# wordclockv0_1.net
KiCad netlist of a schematic drawn in EAGLE
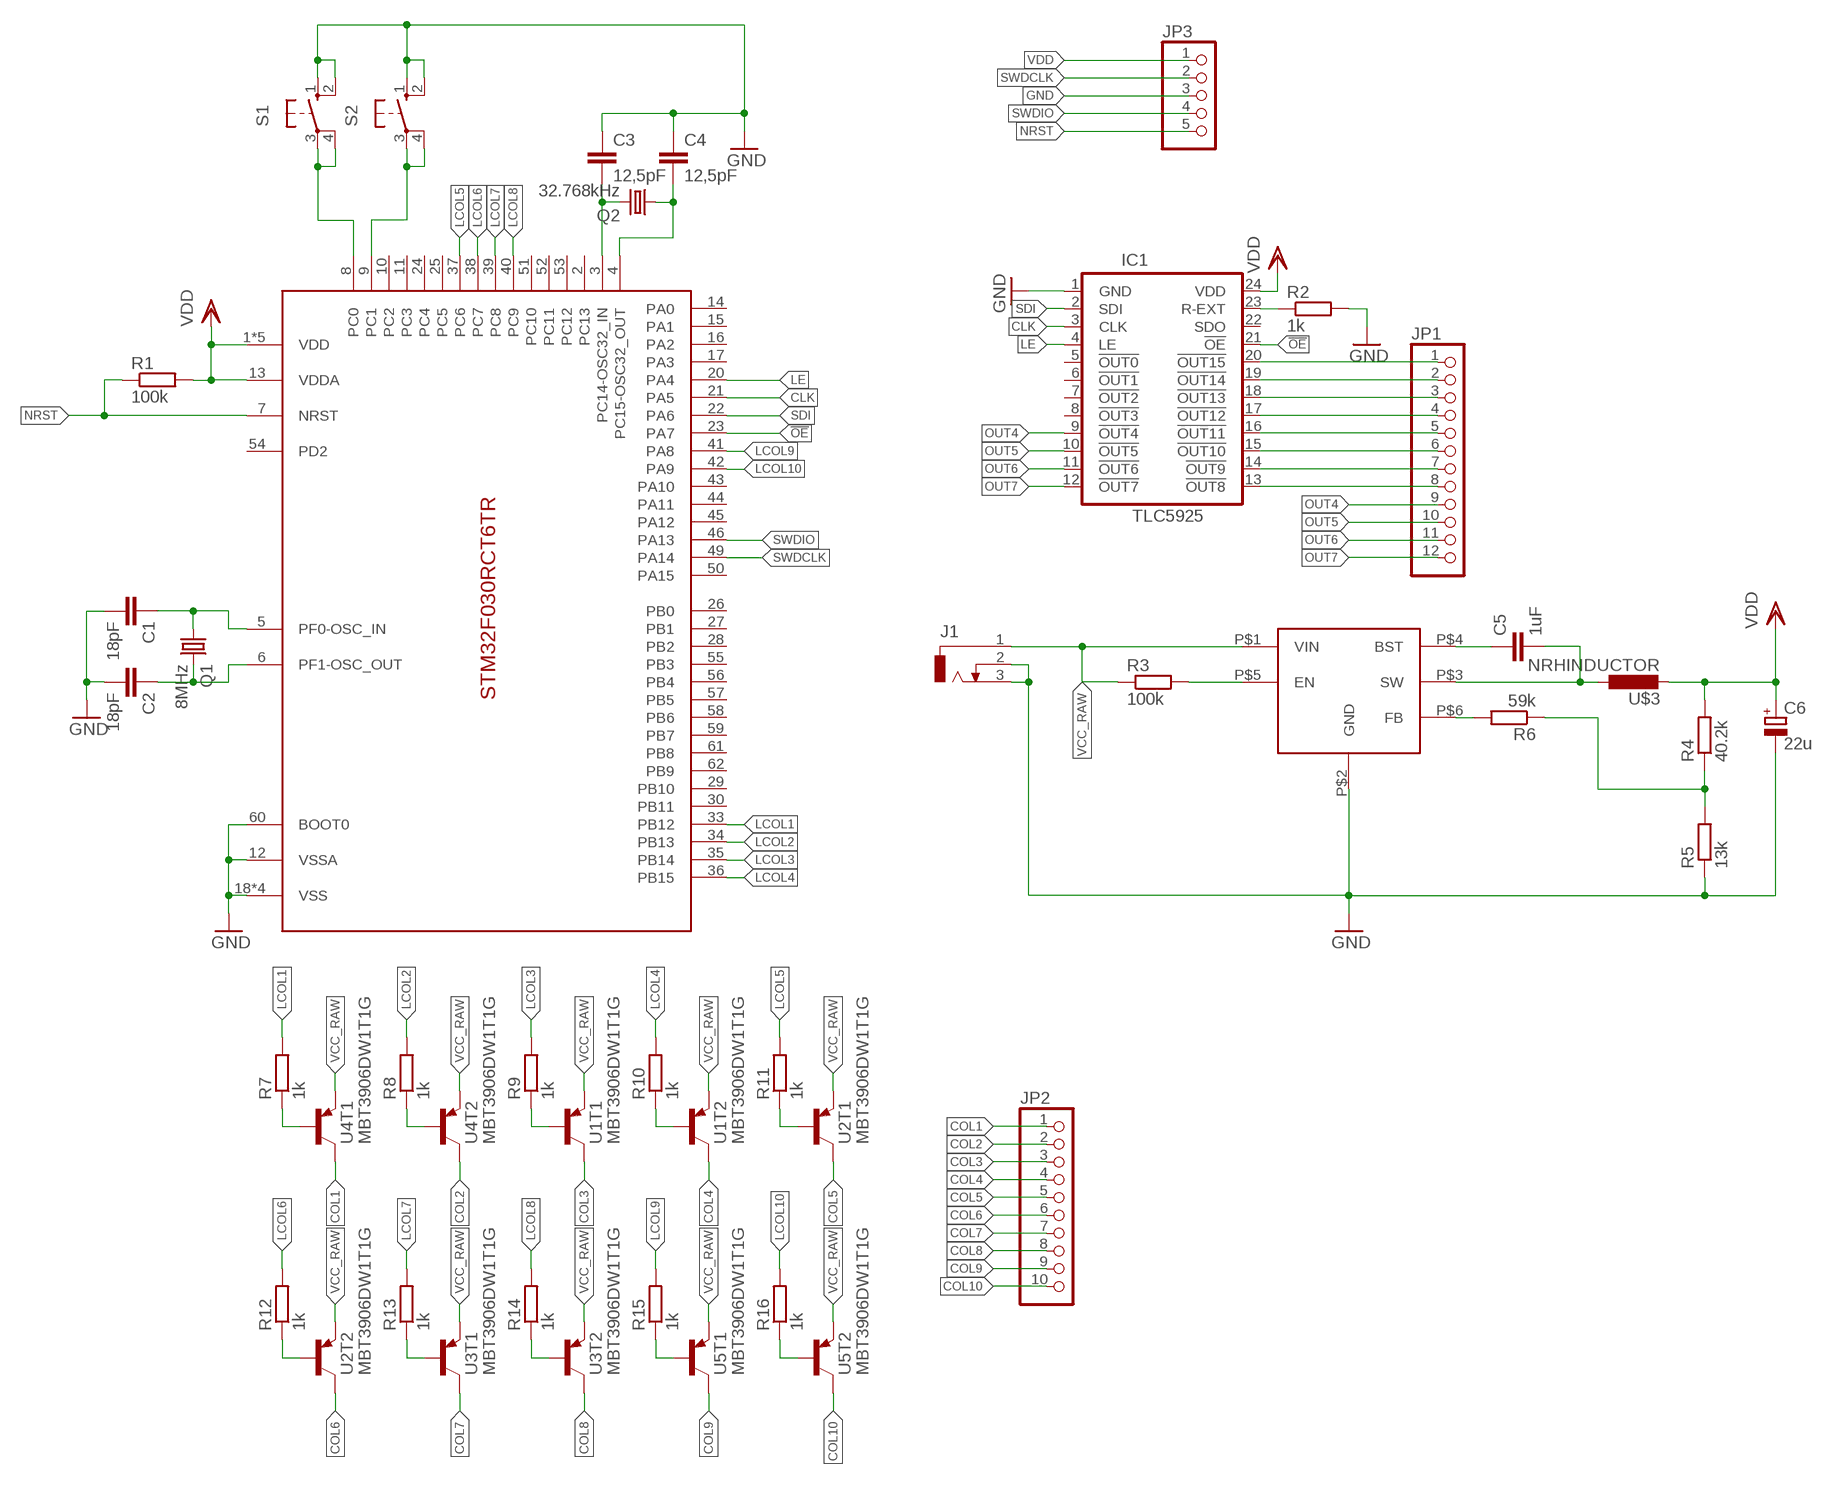
[diagram p0: schematic, sheet 1]

(export (version "E")
  (design (tool "Eeschema 10.0.6"))
  (components
    (comp (ref "C1")
      (value "18pF")
      (footprint "eagle-import:C0402")
      (libsource (lib "eagle-import") (part "C-EUC0402"))
    )
    (comp (ref "C2")
      (value "18pF")
      (footprint "eagle-import:C0402")
      (libsource (lib "eagle-import") (part "rcl_334_C-EUC0402"))
    )
    (comp (ref "C3")
      (value "12,5pF")
      (footprint "eagle-import:C0402")
      (libsource (lib "eagle-import") (part "C-EUC0402"))
    )
    (comp (ref "C4")
      (value "12,5pF")
      (footprint "eagle-import:C0402")
      (libsource (lib "eagle-import") (part "rcl_334_C-EUC0402"))
    )
    (comp (ref "C5")
      (value "1uF")
      (footprint "eagle-import:C0805")
      (libsource (lib "eagle-import") (part "C-EUC0805"))
    )
    (comp (ref "C6")
      (value "22u")
      (footprint "eagle-import:153CLV-0405")
      (libsource (lib "eagle-import") (part "CPOL-EU153CLV-0405"))
    )
    (comp (ref "IC1")
      (value "TLC5925")
      (footprint "eagle-import:SO24W")
      (libsource (lib "eagle-import") (part "TLC5925"))
    )
    (comp (ref "J1")
      (value "DCJ0303")
      (footprint "eagle-import:DCJ0303")
      (libsource (lib "eagle-import") (part "DCJ0303"))
    )
    (comp (ref "JP1")
      (value "PINHD-1X12")
      (footprint "eagle-import:1X12")
      (libsource (lib "eagle-import") (part "PINHD-1X12"))
    )
    (comp (ref "JP2")
      (value "PINHD-1X10")
      (footprint "eagle-import:1X10")
      (libsource (lib "eagle-import") (part "PINHD-1X10"))
    )
    (comp (ref "JP3")
      (value "PINHD-1X5")
      (footprint "eagle-import:1X05")
      (libsource (lib "eagle-import") (part "PINHD-1X5"))
    )
    (comp (ref "Q1")
      (value "8MHz")
      (footprint "eagle-import:HC49U-V")
      (libsource (lib "eagle-import") (part "crystal_204_CRYSTALHC49U-V"))
    )
    (comp (ref "Q2")
      (value "32.768kHz")
      (footprint "eagle-import:TC26V")
      (libsource (lib "eagle-import") (part "CRYSTALTC26V"))
    )
    (comp (ref "R1")
      (value "100k")
      (footprint "eagle-import:M1206")
      (libsource (lib "eagle-import") (part "R-EU_M1206"))
    )
    (comp (ref "R2")
      (value "1k")
      (footprint "eagle-import:M1206")
      (libsource (lib "eagle-import") (part "R-EU_M1206"))
    )
    (comp (ref "R3")
      (value "100k")
      (footprint "eagle-import:M1206")
      (libsource (lib "eagle-import") (part "R-EU_M1206"))
    )
    (comp (ref "R4")
      (value "40.2k")
      (footprint "eagle-import:M1206")
      (libsource (lib "eagle-import") (part "R-EU_M1206"))
    )
    (comp (ref "R5")
      (value "13k")
      (footprint "eagle-import:M1206")
      (libsource (lib "eagle-import") (part "R-EU_M1206"))
    )
    (comp (ref "R6")
      (value "59k")
      (footprint "eagle-import:M1206")
      (libsource (lib "eagle-import") (part "R-EU_M1206"))
    )
    (comp (ref "R7")
      (value "1k")
      (footprint "eagle-import:M1206")
      (libsource (lib "eagle-import") (part "R-EU_M1206"))
    )
    (comp (ref "R8")
      (value "1k")
      (footprint "eagle-import:M1206")
      (libsource (lib "eagle-import") (part "R-EU_M1206"))
    )
    (comp (ref "R9")
      (value "1k")
      (footprint "eagle-import:M1206")
      (libsource (lib "eagle-import") (part "R-EU_M1206"))
    )
    (comp (ref "R10")
      (value "1k")
      (footprint "eagle-import:M1206")
      (libsource (lib "eagle-import") (part "R-EU_M1206"))
    )
    (comp (ref "R11")
      (value "1k")
      (footprint "eagle-import:M1206")
      (libsource (lib "eagle-import") (part "R-EU_M1206"))
    )
    (comp (ref "R12")
      (value "1k")
      (footprint "eagle-import:M1206")
      (libsource (lib "eagle-import") (part "R-EU_M1206"))
    )
    (comp (ref "R13")
      (value "1k")
      (footprint "eagle-import:M1206")
      (libsource (lib "eagle-import") (part "R-EU_M1206"))
    )
    (comp (ref "R14")
      (value "1k")
      (footprint "eagle-import:M1206")
      (libsource (lib "eagle-import") (part "R-EU_M1206"))
    )
    (comp (ref "R15")
      (value "1k")
      (footprint "eagle-import:M1206")
      (libsource (lib "eagle-import") (part "R-EU_M1206"))
    )
    (comp (ref "R16")
      (value "1k")
      (footprint "eagle-import:M1206")
      (libsource (lib "eagle-import") (part "R-EU_M1206"))
    )
    (comp (ref "S1")
      (value "10-XX")
      (footprint "eagle-import:B3F-10XX")
      (fields (field (name "MPN") "B3F-1000"))
      (libsource (lib "eagle-import") (part "10-XX"))
    )
    (comp (ref "S2")
      (value "10-XX")
      (footprint "eagle-import:B3F-10XX")
      (fields (field (name "MPN") "B3F-1000"))
      (libsource (lib "eagle-import") (part "10-XX"))
    )
    (comp (ref "U$1")
      (value "STM32F030RCT6TRLQFP64")
      (footprint "eagle-import:LQFP64")
      (libsource (lib "eagle-import") (part "STM32F030RCT6TRLQFP64"))
    )
    (comp (ref "U$2")
      (value "AP65111A")
      (footprint "eagle-import:TSOT26")
      (libsource (lib "eagle-import") (part "AP65111A"))
    )
    (comp (ref "U$3")
      (value "NRHINDUCTOR")
      (footprint "eagle-import:NRHINDUCTOR")
      (libsource (lib "eagle-import") (part "NRHINDUCTOR"))
    )
    (comp (ref "U1")
      (value "MBT3906DW1T1G")
      (footprint "eagle-import:SOT363-INFINION")
      (libsource (lib "eagle-import") (part "MBT3906DW1T1G"))
    )
    (comp (ref "U2")
      (value "MBT3906DW1T1G")
      (footprint "eagle-import:SOT363-INFINION")
      (libsource (lib "eagle-import") (part "MBT3906DW1T1G"))
    )
    (comp (ref "U3")
      (value "MBT3906DW1T1G")
      (footprint "eagle-import:SOT363-INFINION")
      (libsource (lib "eagle-import") (part "MBT3906DW1T1G"))
    )
    (comp (ref "U4")
      (value "MBT3906DW1T1G")
      (footprint "eagle-import:SOT363-INFINION")
      (libsource (lib "eagle-import") (part "MBT3906DW1T1G"))
    )
    (comp (ref "U5")
      (value "MBT3906DW1T1G")
      (footprint "eagle-import:SOT363-INFINION")
      (libsource (lib "eagle-import") (part "MBT3906DW1T1G"))
    )
  )
  (nets
    (net (code "1") (name "/~{OE}") (class "Default")
      (node (ref "IC1") (pin "21") (pinfunction "~{OE}_21") (pintype "bidirectional"))
      (node (ref "U$1") (pin "23") (pinfunction "PA7_23") (pintype "bidirectional"))
    )
    (net (code "2") (name "CLK") (class "Default")
      (node (ref "IC1") (pin "3") (pinfunction "CLK_3") (pintype "input"))
      (node (ref "U$1") (pin "21") (pinfunction "PA5_21") (pintype "bidirectional"))
    )
    (net (code "3") (name "COL1") (class "Default")
      (node (ref "JP2") (pin "1") (pinfunction "1_1") (pintype "passive"))
      (node (ref "U4") (pin "6") (pinfunction "C_6") (pintype "passive"))
    )
    (net (code "4") (name "COL2") (class "Default")
      (node (ref "JP2") (pin "2") (pinfunction "2_2") (pintype "passive"))
      (node (ref "U4") (pin "3") (pinfunction "C_3") (pintype "passive"))
    )
    (net (code "5") (name "COL3") (class "Default")
      (node (ref "JP2") (pin "3") (pinfunction "3_3") (pintype "passive"))
      (node (ref "U1") (pin "6") (pinfunction "C_6") (pintype "passive"))
    )
    (net (code "6") (name "COL4") (class "Default")
      (node (ref "JP2") (pin "4") (pinfunction "4_4") (pintype "passive"))
      (node (ref "U1") (pin "3") (pinfunction "C_3") (pintype "passive"))
    )
    (net (code "7") (name "COL5") (class "Default")
      (node (ref "JP2") (pin "5") (pinfunction "5_5") (pintype "passive"))
      (node (ref "U2") (pin "6") (pinfunction "C_6") (pintype "passive"))
    )
    (net (code "8") (name "COL6") (class "Default")
      (node (ref "JP2") (pin "6") (pinfunction "6_6") (pintype "passive"))
      (node (ref "U2") (pin "3") (pinfunction "C_3") (pintype "passive"))
    )
    (net (code "9") (name "COL7") (class "Default")
      (node (ref "JP2") (pin "7") (pinfunction "7_7") (pintype "passive"))
      (node (ref "U3") (pin "6") (pinfunction "C_6") (pintype "passive"))
    )
    (net (code "10") (name "COL8") (class "Default")
      (node (ref "JP2") (pin "8") (pinfunction "8_8") (pintype "passive"))
      (node (ref "U3") (pin "3") (pinfunction "C_3") (pintype "passive"))
    )
    (net (code "11") (name "COL9") (class "Default")
      (node (ref "JP2") (pin "9") (pinfunction "9_9") (pintype "passive"))
      (node (ref "U5") (pin "6") (pinfunction "C_6") (pintype "passive"))
    )
    (net (code "12") (name "COL10") (class "Default")
      (node (ref "JP2") (pin "10") (pinfunction "10_10") (pintype "passive"))
      (node (ref "U5") (pin "3") (pinfunction "C_3") (pintype "passive"))
    )
    (net (code "13") (name "GND") (class "Default")
      (node (ref "C1") (pin "2") (pinfunction "2_2") (pintype "passive"))
      (node (ref "C2") (pin "2") (pinfunction "2_2") (pintype "passive"))
      (node (ref "C3") (pin "1") (pinfunction "1_1") (pintype "passive"))
      (node (ref "C4") (pin "1") (pinfunction "1_1") (pintype "passive"))
      (node (ref "C6") (pin "-") (pinfunction "-_-") (pintype "passive"))
      (node (ref "IC1") (pin "1") (pinfunction "GND_1") (pintype "power_in"))
      (node (ref "J1") (pin "2") (pinfunction "2_2") (pintype "passive"))
      (node (ref "J1") (pin "3") (pinfunction "3_3") (pintype "passive"))
      (node (ref "JP3") (pin "3") (pinfunction "3_3") (pintype "passive"))
      (node (ref "R2") (pin "2") (pinfunction "2_2") (pintype "passive"))
      (node (ref "R5") (pin "1") (pinfunction "1_1") (pintype "passive"))
      (node (ref "S1") (pin "1") (pinfunction "S_1") (pintype "passive"))
      (node (ref "S1") (pin "2") (pinfunction "S1_2") (pintype "passive"))
      (node (ref "S2") (pin "1") (pinfunction "S_1") (pintype "passive"))
      (node (ref "S2") (pin "2") (pinfunction "S1_2") (pintype "passive"))
      (node (ref "U$1") (pin "12") (pinfunction "VSSA_12") (pintype "bidirectional"))
      (node (ref "U$1") (pin "18") (pinfunction "VSS_18") (pintype "bidirectional"))
      (node (ref "U$1") (pin "31") (pinfunction "VSS_31") (pintype "bidirectional"))
      (node (ref "U$1") (pin "47") (pinfunction "VSS_47") (pintype "bidirectional"))
      (node (ref "U$1") (pin "60") (pinfunction "BOOT0_60") (pintype "bidirectional"))
      (node (ref "U$1") (pin "63") (pinfunction "VSS_63") (pintype "bidirectional"))
      (node (ref "U$2") (pin "P$2") (pinfunction "GND_P$2") (pintype "bidirectional"))
    )
    (net (code "14") (name "LCOL1") (class "Default")
      (node (ref "R7") (pin "2") (pinfunction "2_2") (pintype "passive"))
      (node (ref "U$1") (pin "33") (pinfunction "PB12_33") (pintype "bidirectional"))
    )
    (net (code "15") (name "LCOL2") (class "Default")
      (node (ref "R8") (pin "2") (pinfunction "2_2") (pintype "passive"))
      (node (ref "U$1") (pin "34") (pinfunction "PB13_34") (pintype "bidirectional"))
    )
    (net (code "16") (name "LCOL3") (class "Default")
      (node (ref "R9") (pin "2") (pinfunction "2_2") (pintype "passive"))
      (node (ref "U$1") (pin "35") (pinfunction "PB14_35") (pintype "bidirectional"))
    )
    (net (code "17") (name "LCOL4") (class "Default")
      (node (ref "R10") (pin "2") (pinfunction "2_2") (pintype "passive"))
      (node (ref "U$1") (pin "36") (pinfunction "PB15_36") (pintype "bidirectional"))
    )
    (net (code "18") (name "LCOL5") (class "Default")
      (node (ref "R11") (pin "2") (pinfunction "2_2") (pintype "passive"))
      (node (ref "U$1") (pin "37") (pinfunction "PC6_37") (pintype "bidirectional"))
    )
    (net (code "19") (name "LCOL6") (class "Default")
      (node (ref "R12") (pin "2") (pinfunction "2_2") (pintype "passive"))
      (node (ref "U$1") (pin "38") (pinfunction "PC7_38") (pintype "bidirectional"))
    )
    (net (code "20") (name "LCOL7") (class "Default")
      (node (ref "R13") (pin "2") (pinfunction "2_2") (pintype "passive"))
      (node (ref "U$1") (pin "39") (pinfunction "PC8_39") (pintype "bidirectional"))
    )
    (net (code "21") (name "LCOL8") (class "Default")
      (node (ref "R14") (pin "2") (pinfunction "2_2") (pintype "passive"))
      (node (ref "U$1") (pin "40") (pinfunction "PC9_40") (pintype "bidirectional"))
    )
    (net (code "22") (name "LCOL9") (class "Default")
      (node (ref "R15") (pin "2") (pinfunction "2_2") (pintype "passive"))
      (node (ref "U$1") (pin "41") (pinfunction "PA8_41") (pintype "bidirectional"))
    )
    (net (code "23") (name "LCOL10") (class "Default")
      (node (ref "R16") (pin "2") (pinfunction "2_2") (pintype "passive"))
      (node (ref "U$1") (pin "42") (pinfunction "PA9_42") (pintype "bidirectional"))
    )
    (net (code "24") (name "LE") (class "Default")
      (node (ref "IC1") (pin "4") (pinfunction "LE_4") (pintype "bidirectional"))
      (node (ref "U$1") (pin "20") (pinfunction "PA4_20") (pintype "bidirectional"))
    )
    (net (code "25") (name "NRST") (class "Default")
      (node (ref "JP3") (pin "5") (pinfunction "5_5") (pintype "passive"))
      (node (ref "R1") (pin "1") (pinfunction "1_1") (pintype "passive"))
      (node (ref "U$1") (pin "7") (pinfunction "NRST_7") (pintype "bidirectional"))
    )
    (net (code "26") (name "Net-(IC1-R-EXT)") (class "Default")
      (node (ref "IC1") (pin "23") (pinfunction "R-EXT_23") (pintype "passive"))
      (node (ref "R2") (pin "1") (pinfunction "1_1") (pintype "passive"))
    )
    (net (code "27") (name "Net-(IC1-~{OUT8})") (class "Default")
      (node (ref "IC1") (pin "13") (pinfunction "~{OUT8}_13") (pintype "bidirectional"))
      (node (ref "JP1") (pin "8") (pinfunction "8_8") (pintype "passive"))
    )
    (net (code "28") (name "Net-(IC1-~{OUT9})") (class "Default")
      (node (ref "IC1") (pin "14") (pinfunction "~{OUT9}_14") (pintype "bidirectional"))
      (node (ref "JP1") (pin "7") (pinfunction "7_7") (pintype "passive"))
    )
    (net (code "29") (name "Net-(IC1-~{OUT10})") (class "Default")
      (node (ref "IC1") (pin "15") (pinfunction "~{OUT10}_15") (pintype "bidirectional"))
      (node (ref "JP1") (pin "6") (pinfunction "6_6") (pintype "passive"))
    )
    (net (code "30") (name "Net-(IC1-~{OUT11})") (class "Default")
      (node (ref "IC1") (pin "16") (pinfunction "~{OUT11}_16") (pintype "bidirectional"))
      (node (ref "JP1") (pin "5") (pinfunction "5_5") (pintype "passive"))
    )
    (net (code "31") (name "Net-(IC1-~{OUT12})") (class "Default")
      (node (ref "IC1") (pin "17") (pinfunction "~{OUT12}_17") (pintype "bidirectional"))
      (node (ref "JP1") (pin "4") (pinfunction "4_4") (pintype "passive"))
    )
    (net (code "32") (name "Net-(IC1-~{OUT13})") (class "Default")
      (node (ref "IC1") (pin "18") (pinfunction "~{OUT13}_18") (pintype "bidirectional"))
      (node (ref "JP1") (pin "3") (pinfunction "3_3") (pintype "passive"))
    )
    (net (code "33") (name "Net-(IC1-~{OUT14})") (class "Default")
      (node (ref "IC1") (pin "19") (pinfunction "~{OUT14}_19") (pintype "bidirectional"))
      (node (ref "JP1") (pin "2") (pinfunction "2_2") (pintype "passive"))
    )
    (net (code "34") (name "Net-(IC1-~{OUT15})") (class "Default")
      (node (ref "IC1") (pin "20") (pinfunction "~{OUT15}_20") (pintype "bidirectional"))
      (node (ref "JP1") (pin "1") (pinfunction "1_1") (pintype "passive"))
    )
    (net (code "35") (name "Net-(R4-Pad1)") (class "Default")
      (node (ref "R4") (pin "1") (pinfunction "1_1") (pintype "passive"))
      (node (ref "R5") (pin "2") (pinfunction "2_2") (pintype "passive"))
      (node (ref "R6") (pin "1") (pinfunction "1_1") (pintype "passive"))
    )
    (net (code "36") (name "Net-(S1-P)") (class "Default")
      (node (ref "S1") (pin "3") (pinfunction "P_3") (pintype "passive"))
      (node (ref "S1") (pin "4") (pinfunction "P1_4") (pintype "passive"))
      (node (ref "U$1") (pin "8") (pinfunction "PC0_8") (pintype "bidirectional"))
    )
    (net (code "37") (name "Net-(S2-P)") (class "Default")
      (node (ref "S2") (pin "3") (pinfunction "P_3") (pintype "passive"))
      (node (ref "S2") (pin "4") (pinfunction "P1_4") (pintype "passive"))
      (node (ref "U$1") (pin "9") (pinfunction "PC1_9") (pintype "bidirectional"))
    )
    (net (code "38") (name "Net-(U$1-PC14-OSC32_IN)") (class "Default")
      (node (ref "C3") (pin "2") (pinfunction "2_2") (pintype "passive"))
      (node (ref "Q2") (pin "2") (pinfunction "2_2") (pintype "passive"))
      (node (ref "U$1") (pin "3") (pinfunction "PC14-OSC32_IN_3") (pintype "bidirectional"))
    )
    (net (code "39") (name "Net-(U$1-PC15-OSC32_OUT)") (class "Default")
      (node (ref "C4") (pin "2") (pinfunction "2_2") (pintype "passive"))
      (node (ref "Q2") (pin "1") (pinfunction "1_1") (pintype "passive"))
      (node (ref "U$1") (pin "4") (pinfunction "PC15-OSC32_OUT_4") (pintype "bidirectional"))
    )
    (net (code "40") (name "Net-(U$1-PF0-OSC_IN)") (class "Default")
      (node (ref "C1") (pin "1") (pinfunction "1_1") (pintype "passive"))
      (node (ref "Q1") (pin "1") (pinfunction "1_1") (pintype "passive"))
      (node (ref "U$1") (pin "5") (pinfunction "PF0-OSC_IN_5") (pintype "bidirectional"))
    )
    (net (code "41") (name "Net-(U$1-PF1-OSC_OUT)") (class "Default")
      (node (ref "C2") (pin "1") (pinfunction "1_1") (pintype "passive"))
      (node (ref "Q1") (pin "2") (pinfunction "2_2") (pintype "passive"))
      (node (ref "U$1") (pin "6") (pinfunction "PF1-OSC_OUT_6") (pintype "bidirectional"))
    )
    (net (code "42") (name "Net-(U$2-BST)") (class "Default")
      (node (ref "C5") (pin "1") (pinfunction "1_1") (pintype "passive"))
      (node (ref "U$2") (pin "P$4") (pinfunction "BST_P$4") (pintype "bidirectional"))
    )
    (net (code "43") (name "Net-(U$2-EN)") (class "Default")
      (node (ref "R3") (pin "2") (pinfunction "2_2") (pintype "passive"))
      (node (ref "U$2") (pin "P$5") (pinfunction "EN_P$5") (pintype "bidirectional"))
    )
    (net (code "44") (name "Net-(U$2-FB)") (class "Default")
      (node (ref "R6") (pin "2") (pinfunction "2_2") (pintype "passive"))
      (node (ref "U$2") (pin "P$6") (pinfunction "FB_P$6") (pintype "bidirectional"))
    )
    (net (code "45") (name "Net-(U$2-SW)") (class "Default")
      (node (ref "C5") (pin "2") (pinfunction "2_2") (pintype "passive"))
      (node (ref "U$2") (pin "P$3") (pinfunction "SW_P$3") (pintype "bidirectional"))
      (node (ref "U$3") (pin "P$1") (pinfunction "1_P$1") (pintype "passive"))
    )
    (net (code "46") (name "Net-(U1A-B)") (class "Default")
      (node (ref "R9") (pin "1") (pinfunction "1_1") (pintype "passive"))
      (node (ref "U1") (pin "2") (pinfunction "B_2") (pintype "passive"))
    )
    (net (code "47") (name "Net-(U1B-B)") (class "Default")
      (node (ref "R10") (pin "1") (pinfunction "1_1") (pintype "passive"))
      (node (ref "U1") (pin "5") (pinfunction "B_5") (pintype "passive"))
    )
    (net (code "48") (name "Net-(U2A-B)") (class "Default")
      (node (ref "R11") (pin "1") (pinfunction "1_1") (pintype "passive"))
      (node (ref "U2") (pin "2") (pinfunction "B_2") (pintype "passive"))
    )
    (net (code "49") (name "Net-(U2B-B)") (class "Default")
      (node (ref "R12") (pin "1") (pinfunction "1_1") (pintype "passive"))
      (node (ref "U2") (pin "5") (pinfunction "B_5") (pintype "passive"))
    )
    (net (code "50") (name "Net-(U3A-B)") (class "Default")
      (node (ref "R13") (pin "1") (pinfunction "1_1") (pintype "passive"))
      (node (ref "U3") (pin "2") (pinfunction "B_2") (pintype "passive"))
    )
    (net (code "51") (name "Net-(U3B-B)") (class "Default")
      (node (ref "R14") (pin "1") (pinfunction "1_1") (pintype "passive"))
      (node (ref "U3") (pin "5") (pinfunction "B_5") (pintype "passive"))
    )
    (net (code "52") (name "Net-(U4A-B)") (class "Default")
      (node (ref "R7") (pin "1") (pinfunction "1_1") (pintype "passive"))
      (node (ref "U4") (pin "2") (pinfunction "B_2") (pintype "passive"))
    )
    (net (code "53") (name "Net-(U4B-B)") (class "Default")
      (node (ref "R8") (pin "1") (pinfunction "1_1") (pintype "passive"))
      (node (ref "U4") (pin "5") (pinfunction "B_5") (pintype "passive"))
    )
    (net (code "54") (name "Net-(U5A-B)") (class "Default")
      (node (ref "R15") (pin "1") (pinfunction "1_1") (pintype "passive"))
      (node (ref "U5") (pin "2") (pinfunction "B_2") (pintype "passive"))
    )
    (net (code "55") (name "Net-(U5B-B)") (class "Default")
      (node (ref "R16") (pin "1") (pinfunction "1_1") (pintype "passive"))
      (node (ref "U5") (pin "5") (pinfunction "B_5") (pintype "passive"))
    )
    (net (code "56") (name "OUT4") (class "Default")
      (node (ref "IC1") (pin "9") (pinfunction "~{OUT4}_9") (pintype "bidirectional"))
      (node (ref "JP1") (pin "9") (pinfunction "9_9") (pintype "passive"))
    )
    (net (code "57") (name "OUT5") (class "Default")
      (node (ref "IC1") (pin "10") (pinfunction "~{OUT5}_10") (pintype "bidirectional"))
      (node (ref "JP1") (pin "10") (pinfunction "10_10") (pintype "passive"))
    )
    (net (code "58") (name "OUT6") (class "Default")
      (node (ref "IC1") (pin "11") (pinfunction "~{OUT6}_11") (pintype "bidirectional"))
      (node (ref "JP1") (pin "11") (pinfunction "11_11") (pintype "passive"))
    )
    (net (code "59") (name "OUT7") (class "Default")
      (node (ref "IC1") (pin "12") (pinfunction "~{OUT7}_12") (pintype "bidirectional"))
      (node (ref "JP1") (pin "12") (pinfunction "12_12") (pintype "passive"))
    )
    (net (code "60") (name "SDI") (class "Default")
      (node (ref "IC1") (pin "2") (pinfunction "SDI_2") (pintype "input"))
      (node (ref "U$1") (pin "22") (pinfunction "PA6_22") (pintype "bidirectional"))
    )
    (net (code "61") (name "SWDCLK") (class "Default")
      (node (ref "JP3") (pin "2") (pinfunction "2_2") (pintype "passive"))
      (node (ref "U$1") (pin "49") (pinfunction "PA14_49") (pintype "bidirectional"))
    )
    (net (code "62") (name "SWDIO") (class "Default")
      (node (ref "JP3") (pin "4") (pinfunction "4_4") (pintype "passive"))
      (node (ref "U$1") (pin "46") (pinfunction "PA13_46") (pintype "bidirectional"))
    )
    (net (code "63") (name "VCC_RAW") (class "Default")
      (node (ref "J1") (pin "1") (pinfunction "1_1") (pintype "passive"))
      (node (ref "R3") (pin "1") (pinfunction "1_1") (pintype "passive"))
      (node (ref "U$2") (pin "P$1") (pinfunction "VIN_P$1") (pintype "bidirectional"))
      (node (ref "U1") (pin "1") (pinfunction "E_1") (pintype "passive"))
      (node (ref "U1") (pin "4") (pinfunction "E_4") (pintype "passive"))
      (node (ref "U2") (pin "1") (pinfunction "E_1") (pintype "passive"))
      (node (ref "U2") (pin "4") (pinfunction "E_4") (pintype "passive"))
      (node (ref "U3") (pin "1") (pinfunction "E_1") (pintype "passive"))
      (node (ref "U3") (pin "4") (pinfunction "E_4") (pintype "passive"))
      (node (ref "U4") (pin "1") (pinfunction "E_1") (pintype "passive"))
      (node (ref "U4") (pin "4") (pinfunction "E_4") (pintype "passive"))
      (node (ref "U5") (pin "1") (pinfunction "E_1") (pintype "passive"))
      (node (ref "U5") (pin "4") (pinfunction "E_4") (pintype "passive"))
    )
    (net (code "64") (name "VDD") (class "Default")
      (node (ref "C6") (pin "+") (pinfunction "+_+") (pintype "passive"))
      (node (ref "IC1") (pin "24") (pinfunction "VDD_24") (pintype "power_in"))
      (node (ref "JP3") (pin "1") (pinfunction "1_1") (pintype "passive"))
      (node (ref "R1") (pin "2") (pinfunction "2_2") (pintype "passive"))
      (node (ref "R4") (pin "2") (pinfunction "2_2") (pintype "passive"))
      (node (ref "U$1") (pin "1") (pinfunction "VDD_1") (pintype "bidirectional"))
      (node (ref "U$1") (pin "13") (pinfunction "VDDA_13") (pintype "bidirectional"))
      (node (ref "U$1") (pin "19") (pinfunction "VDD_19") (pintype "bidirectional"))
      (node (ref "U$1") (pin "32") (pinfunction "VDD_32") (pintype "bidirectional"))
      (node (ref "U$1") (pin "48") (pinfunction "VDD_48") (pintype "bidirectional"))
      (node (ref "U$1") (pin "64") (pinfunction "VDD_64") (pintype "bidirectional"))
      (node (ref "U$3") (pin "P$2") (pinfunction "2_P$2") (pintype "passive"))
    )
    (net (code "65") (name "unconnected-(IC1-SDO-Pad22)") (class "Default")
      (node (ref "IC1") (pin "22") (pinfunction "SDO_22") (pintype "output"))
    )
    (net (code "66") (name "unconnected-(IC1-~{OUT0}-Pad5)") (class "Default")
      (node (ref "IC1") (pin "5") (pinfunction "~{OUT0}_5") (pintype "bidirectional"))
    )
    (net (code "67") (name "unconnected-(IC1-~{OUT1}-Pad6)") (class "Default")
      (node (ref "IC1") (pin "6") (pinfunction "~{OUT1}_6") (pintype "bidirectional"))
    )
    (net (code "68") (name "unconnected-(IC1-~{OUT2}-Pad7)") (class "Default")
      (node (ref "IC1") (pin "7") (pinfunction "~{OUT2}_7") (pintype "bidirectional"))
    )
    (net (code "69") (name "unconnected-(IC1-~{OUT3}-Pad8)") (class "Default")
      (node (ref "IC1") (pin "8") (pinfunction "~{OUT3}_8") (pintype "bidirectional"))
    )
    (net (code "70") (name "unconnected-(U$1-PA0-Pad14)") (class "Default")
      (node (ref "U$1") (pin "14") (pinfunction "PA0_14") (pintype "bidirectional"))
    )
    (net (code "71") (name "unconnected-(U$1-PA1-Pad15)") (class "Default")
      (node (ref "U$1") (pin "15") (pinfunction "PA1_15") (pintype "bidirectional"))
    )
    (net (code "72") (name "unconnected-(U$1-PA2-Pad16)") (class "Default")
      (node (ref "U$1") (pin "16") (pinfunction "PA2_16") (pintype "bidirectional"))
    )
    (net (code "73") (name "unconnected-(U$1-PA3-Pad17)") (class "Default")
      (node (ref "U$1") (pin "17") (pinfunction "PA3_17") (pintype "bidirectional"))
    )
    (net (code "74") (name "unconnected-(U$1-PA10-Pad43)") (class "Default")
      (node (ref "U$1") (pin "43") (pinfunction "PA10_43") (pintype "bidirectional"))
    )
    (net (code "75") (name "unconnected-(U$1-PA11-Pad44)") (class "Default")
      (node (ref "U$1") (pin "44") (pinfunction "PA11_44") (pintype "bidirectional"))
    )
    (net (code "76") (name "unconnected-(U$1-PA12-Pad45)") (class "Default")
      (node (ref "U$1") (pin "45") (pinfunction "PA12_45") (pintype "bidirectional"))
    )
    (net (code "77") (name "unconnected-(U$1-PA15-Pad50)") (class "Default")
      (node (ref "U$1") (pin "50") (pinfunction "PA15_50") (pintype "bidirectional"))
    )
    (net (code "78") (name "unconnected-(U$1-PB0-Pad26)") (class "Default")
      (node (ref "U$1") (pin "26") (pinfunction "PB0_26") (pintype "bidirectional"))
    )
    (net (code "79") (name "unconnected-(U$1-PB1-Pad27)") (class "Default")
      (node (ref "U$1") (pin "27") (pinfunction "PB1_27") (pintype "bidirectional"))
    )
    (net (code "80") (name "unconnected-(U$1-PB2-Pad28)") (class "Default")
      (node (ref "U$1") (pin "28") (pinfunction "PB2_28") (pintype "bidirectional"))
    )
    (net (code "81") (name "unconnected-(U$1-PB3-Pad55)") (class "Default")
      (node (ref "U$1") (pin "55") (pinfunction "PB3_55") (pintype "bidirectional"))
    )
    (net (code "82") (name "unconnected-(U$1-PB4-Pad56)") (class "Default")
      (node (ref "U$1") (pin "56") (pinfunction "PB4_56") (pintype "bidirectional"))
    )
    (net (code "83") (name "unconnected-(U$1-PB5-Pad57)") (class "Default")
      (node (ref "U$1") (pin "57") (pinfunction "PB5_57") (pintype "bidirectional"))
    )
    (net (code "84") (name "unconnected-(U$1-PB6-Pad58)") (class "Default")
      (node (ref "U$1") (pin "58") (pinfunction "PB6_58") (pintype "bidirectional"))
    )
    (net (code "85") (name "unconnected-(U$1-PB7-Pad59)") (class "Default")
      (node (ref "U$1") (pin "59") (pinfunction "PB7_59") (pintype "bidirectional"))
    )
    (net (code "86") (name "unconnected-(U$1-PB8-Pad61)") (class "Default")
      (node (ref "U$1") (pin "61") (pinfunction "PB8_61") (pintype "bidirectional"))
    )
    (net (code "87") (name "unconnected-(U$1-PB9-Pad62)") (class "Default")
      (node (ref "U$1") (pin "62") (pinfunction "PB9_62") (pintype "bidirectional"))
    )
    (net (code "88") (name "unconnected-(U$1-PB10-Pad29)") (class "Default")
      (node (ref "U$1") (pin "29") (pinfunction "PB10_29") (pintype "bidirectional"))
    )
    (net (code "89") (name "unconnected-(U$1-PB11-Pad30)") (class "Default")
      (node (ref "U$1") (pin "30") (pinfunction "PB11_30") (pintype "bidirectional"))
    )
    (net (code "90") (name "unconnected-(U$1-PC2-Pad10)") (class "Default")
      (node (ref "U$1") (pin "10") (pinfunction "PC2_10") (pintype "bidirectional"))
    )
    (net (code "91") (name "unconnected-(U$1-PC3-Pad11)") (class "Default")
      (node (ref "U$1") (pin "11") (pinfunction "PC3_11") (pintype "bidirectional"))
    )
    (net (code "92") (name "unconnected-(U$1-PC4-Pad24)") (class "Default")
      (node (ref "U$1") (pin "24") (pinfunction "PC4_24") (pintype "bidirectional"))
    )
    (net (code "93") (name "unconnected-(U$1-PC5-Pad25)") (class "Default")
      (node (ref "U$1") (pin "25") (pinfunction "PC5_25") (pintype "bidirectional"))
    )
    (net (code "94") (name "unconnected-(U$1-PC10-Pad51)") (class "Default")
      (node (ref "U$1") (pin "51") (pinfunction "PC10_51") (pintype "bidirectional"))
    )
    (net (code "95") (name "unconnected-(U$1-PC11-Pad52)") (class "Default")
      (node (ref "U$1") (pin "52") (pinfunction "PC11_52") (pintype "bidirectional"))
    )
    (net (code "96") (name "unconnected-(U$1-PC12-Pad53)") (class "Default")
      (node (ref "U$1") (pin "53") (pinfunction "PC12_53") (pintype "bidirectional"))
    )
    (net (code "97") (name "unconnected-(U$1-PC13-Pad2)") (class "Default")
      (node (ref "U$1") (pin "2") (pinfunction "PC13_2") (pintype "bidirectional"))
    )
    (net (code "98") (name "unconnected-(U$1-PD2-Pad54)") (class "Default")
      (node (ref "U$1") (pin "54") (pinfunction "PD2_54") (pintype "bidirectional"))
    )
  )
)
